# PiHAT_v0_3.net
KiCad netlist of a schematic drawn in EAGLE
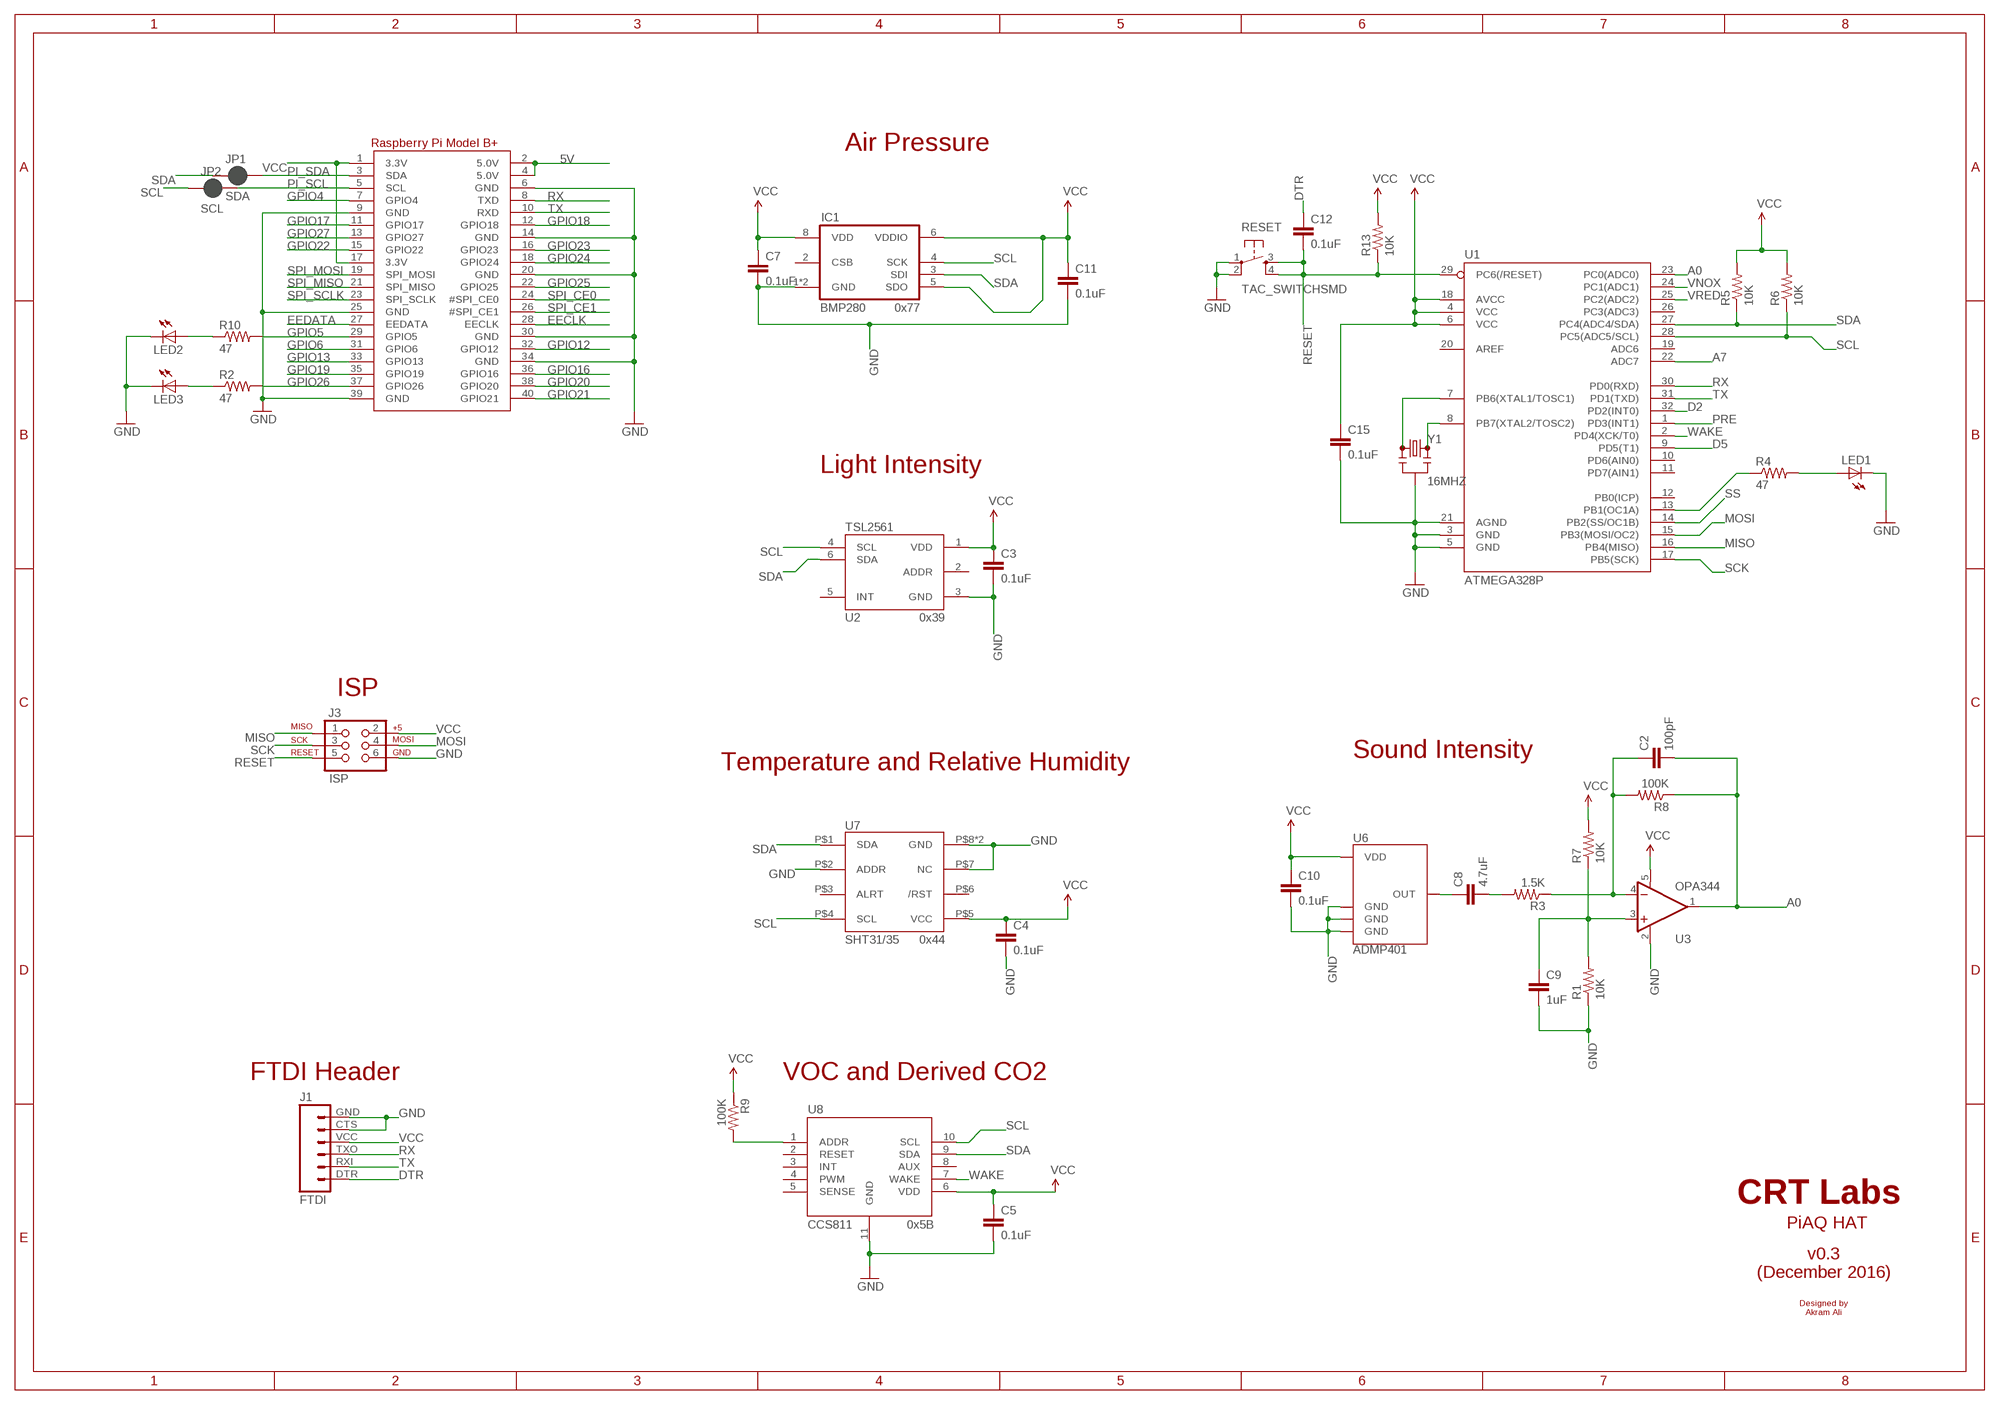
[diagram p0: schematic, sheet 1]

(export (version "E")
  (design (tool "Eeschema 10.0.6"))
  (components
    (comp (ref "C2")
      (value "100pF")
      (footprint "eagle-import:0805")
      (fields (field (name "MPN") "CC0805JRNPO9BN101"))
      (libsource (lib "eagle-import") (part "CAP0805"))
    )
    (comp (ref "C3")
      (value "0.1uF")
      (footprint "eagle-import:0805")
      (fields (field (name "MPN") "CC0603KRX7R7BB104"))
      (libsource (lib "eagle-import") (part "SparkFun-Passives_CAP0805"))
    )
    (comp (ref "C4")
      (value "0.1uF")
      (footprint "eagle-import:0805")
      (fields (field (name "MPN") "CC0603KRX7R7BB104"))
      (libsource (lib "eagle-import") (part "SparkFun-Passives_CAP0805"))
    )
    (comp (ref "C5")
      (value "0.1uF")
      (footprint "eagle-import:0805")
      (fields (field (name "MPN") "CC0603KRX7R7BB104"))
      (libsource (lib "eagle-import") (part "SparkFun-Passives_CAP0805"))
    )
    (comp (ref "C7")
      (value "0.1uF")
      (footprint "eagle-import:0805")
      (fields (field (name "MPN") "CC0603KRX7R7BB104"))
      (libsource (lib "eagle-import") (part "SparkFun-Passives_CAP0805"))
    )
    (comp (ref "C8")
      (value "4.7uF")
      (footprint "eagle-import:0805")
      (fields (field (name "MPN") "CC0805KKX5R8BB475"))
      (libsource (lib "eagle-import") (part "CAP0805"))
    )
    (comp (ref "C9")
      (value "1uF")
      (footprint "eagle-import:0805")
      (fields (field (name "MPN") "CC0805KKX7R7BB105"))
      (libsource (lib "eagle-import") (part "CAP0805"))
    )
    (comp (ref "C10")
      (value "0.1uF")
      (footprint "eagle-import:0805")
      (fields (field (name "MPN") "CC0603KRX7R7BB104"))
      (libsource (lib "eagle-import") (part "CAP0805"))
    )
    (comp (ref "C11")
      (value "0.1uF")
      (footprint "eagle-import:0805")
      (fields (field (name "MPN") "CC0603KRX7R7BB104"))
      (libsource (lib "eagle-import") (part "SparkFun-Passives_CAP0805"))
    )
    (comp (ref "C12")
      (value "0.1uF")
      (footprint "eagle-import:0805")
      (fields (field (name "MPN") "CC0603KRX7R7BB104"))
      (libsource (lib "eagle-import") (part "SparkFun-Passives_CAP0805"))
    )
    (comp (ref "C15")
      (value "0.1uF")
      (footprint "eagle-import:0805")
      (fields (field (name "MPN") "CC0603KRX7R7BB104"))
      (libsource (lib "eagle-import") (part "SparkFun-Passives_CAP0805"))
    )
    (comp (ref "IC1")
      (value "BMP280")
      (footprint "eagle-import:BMP280")
      (libsource (lib "eagle-import") (part "BMP280"))
    )
    (comp (ref "J1")
      (value "FTDI")
      (footprint "eagle-import:FTDI_BASIC")
      (libsource (lib "eagle-import") (part "FTDI_BASICPTH"))
    )
    (comp (ref "J3")
      (value "ISP")
      (footprint "eagle-import:2X3")
      (libsource (lib "eagle-import") (part "AVR_SPI_PRG_6PTH"))
    )
    (comp (ref "JP1")
      (value "SDA")
      (footprint "eagle-import:PAD-JUMPER-2-NC_BY_PASTE_YES_SILK_FULL_BOX")
      (libsource (lib "eagle-import") (part "JUMPER-PAD-2-NC_BY_PASTEFULL-BOX-SILK"))
    )
    (comp (ref "JP2")
      (value "SCL")
      (footprint "eagle-import:PAD-JUMPER-2-NC_BY_PASTE_YES_SILK_FULL_BOX")
      (libsource (lib "eagle-import") (part "JUMPER-PAD-2-NC_BY_PASTEFULL-BOX-SILK"))
    )
    (comp (ref "LED1")
      (value "LEDCHIPLED_0805")
      (footprint "eagle-import:CHIPLED_0805")
      (fields (field (name "MPN") "LTST-C170TBKT"))
      (libsource (lib "eagle-import") (part "LEDCHIPLED_0805"))
    )
    (comp (ref "LED2")
      (value "LEDCHIPLED_0805")
      (footprint "eagle-import:CHIPLED_0805")
      (fields (field (name "MPN") "LTST-C170TBKT"))
      (libsource (lib "eagle-import") (part "LEDCHIPLED_0805"))
    )
    (comp (ref "LED3")
      (value "LEDCHIPLED_0805")
      (footprint "eagle-import:CHIPLED_0805")
      (fields (field (name "MPN") "LTST-C170TBKT"))
      (libsource (lib "eagle-import") (part "LEDCHIPLED_0805"))
    )
    (comp (ref "R1")
      (value "10K")
      (footprint "eagle-import:0805")
      (fields (field (name "MPN") "RC0805JR-0710KL"))
      (libsource (lib "eagle-import") (part "RESISTOR0805-RES"))
    )
    (comp (ref "R2")
      (value "47")
      (footprint "eagle-import:0805")
      (fields (field (name "MPN") "RC0805JR-0747RL"))
      (libsource (lib "eagle-import") (part "SparkFun-Resistors_RESISTOR0805-RES"))
    )
    (comp (ref "R3")
      (value "1.5K")
      (footprint "eagle-import:0805")
      (fields (field (name "MPN") "RT0805BRD071K5L"))
      (libsource (lib "eagle-import") (part "RESISTOR0805-RES"))
    )
    (comp (ref "R4")
      (value "47")
      (footprint "eagle-import:0805")
      (fields (field (name "MPN") "RC0805JR-0747RL"))
      (libsource (lib "eagle-import") (part "SparkFun-Resistors_RESISTOR0805-RES"))
    )
    (comp (ref "R5")
      (value "10K")
      (footprint "eagle-import:0805")
      (fields (field (name "MPN") "RC0805JR-0710KL"))
      (libsource (lib "eagle-import") (part "SparkFun-Resistors_RESISTOR0805-RES"))
    )
    (comp (ref "R6")
      (value "10K")
      (footprint "eagle-import:0805")
      (fields (field (name "MPN") "RC0805JR-0710KL"))
      (libsource (lib "eagle-import") (part "SparkFun-Resistors_RESISTOR0805-RES"))
    )
    (comp (ref "R7")
      (value "10K")
      (footprint "eagle-import:0805")
      (fields (field (name "MPN") "RC0805JR-0710KL"))
      (libsource (lib "eagle-import") (part "RESISTOR0805-RES"))
    )
    (comp (ref "R8")
      (value "100K")
      (footprint "eagle-import:0805")
      (fields (field (name "MPN") "RC0805FR-07100KL"))
      (libsource (lib "eagle-import") (part "RESISTOR0805-RES"))
    )
    (comp (ref "R9")
      (value "100K")
      (footprint "eagle-import:0805")
      (fields (field (name "MPN") "RC0805FR-07100KL"))
      (libsource (lib "eagle-import") (part "RESISTOR0805-RES"))
    )
    (comp (ref "R10")
      (value "47")
      (footprint "eagle-import:0805")
      (fields (field (name "MPN") "RC0805JR-0747RL"))
      (libsource (lib "eagle-import") (part "SparkFun-Resistors_RESISTOR0805-RES"))
    )
    (comp (ref "R13")
      (value "10K")
      (footprint "eagle-import:0805")
      (fields (field (name "MPN") "RC0805JR-0710KL"))
      (libsource (lib "eagle-import") (part "RESISTOR0805-RES"))
    )
    (comp (ref "RESET")
      (value "TAC_SWITCHSMD")
      (footprint "eagle-import:TACTILE-SWITCH-SMD")
      (fields (field (name "MPN") "PTS525SM15SMTR2 LFS"))
      (libsource (lib "eagle-import") (part "TAC_SWITCHSMD"))
    )
    (comp (ref "RPI1")
      (value "RASPBERRYPI_BPLUS_HATSLOTS")
      (footprint "eagle-import:PI_HAT_SLOTS")
      (libsource (lib "eagle-import") (part "RASPBERRYPI_BPLUS_HATSLOTS"))
    )
    (comp (ref "U1")
      (value "ATMEGA328P")
      (footprint "eagle-import:TQFP32-08")
      (fields (field (name "MPN") "ATMEGA328PB-AU"))
      (libsource (lib "eagle-import") (part "ATMEGA328P_TQFP"))
    )
    (comp (ref "U2")
      (value "TSL2561")
      (footprint "eagle-import:FN-6")
      (fields (field (name "MPN") "TSL2561FN"))
      (libsource (lib "eagle-import") (part "TSL2561FN"))
    )
    (comp (ref "U3")
      (value "OPA344")
      (footprint "eagle-import:SOT23-5")
      (fields (field (name "MPN") "OPA344NA/3K"))
      (libsource (lib "eagle-import") (part "OPA344"))
    )
    (comp (ref "U6")
      (value "ADMP401")
      (footprint "eagle-import:ADMP401")
      (fields (field (name "MPN") "INMP401ACEZ-R7"))
      (libsource (lib "eagle-import") (part "ADMP401"))
    )
    (comp (ref "U7")
      (value "SHT31/35")
      (footprint "eagle-import:SHT3X")
      (fields (field (name "MPN") "SHT31-DIS-B"))
      (libsource (lib "eagle-import") (part "SHT31-DIS"))
    )
    (comp (ref "U8")
      (value "CCS811")
      (footprint "eagle-import:LGA")
      (libsource (lib "eagle-import") (part "CCS811-I2C"))
    )
    (comp (ref "Y1")
      (value "16MHZ")
      (footprint "eagle-import:RESONATOR-SMD")
      (fields (field (name "MPN") "CSTCE16M0V53-R0"))
      (libsource (lib "eagle-import") (part "RESONATOR16MHZ"))
    )
  )
  (nets
    (net (code "1") (name "/5V") (class "Default")
      (node (ref "RPI1") (pin "2") (pinfunction "5.0V_2") (pintype "power_in"))
      (node (ref "RPI1") (pin "4") (pinfunction "5.0V_4") (pintype "power_in"))
    )
    (net (code "2") (name "/EECLK") (class "Default")
      (node (ref "RPI1") (pin "28") (pinfunction "EECLK_28") (pintype "power_in"))
    )
    (net (code "3") (name "/EEDATA") (class "Default")
      (node (ref "RPI1") (pin "27") (pinfunction "EEDATA_27") (pintype "bidirectional"))
    )
    (net (code "4") (name "/GPIO4") (class "Default")
      (node (ref "RPI1") (pin "7") (pinfunction "GPIO4_7") (pintype "bidirectional"))
    )
    (net (code "5") (name "/GPIO5") (class "Default")
      (node (ref "R10") (pin "2") (pinfunction "2_2") (pintype "passive"))
      (node (ref "RPI1") (pin "29") (pinfunction "GPIO5_29") (pintype "bidirectional"))
    )
    (net (code "6") (name "/GPIO6") (class "Default")
      (node (ref "RPI1") (pin "31") (pinfunction "GPIO6_31") (pintype "power_in"))
    )
    (net (code "7") (name "/GPIO12") (class "Default")
      (node (ref "RPI1") (pin "32") (pinfunction "GPIO12_32") (pintype "bidirectional"))
    )
    (net (code "8") (name "/GPIO13") (class "Default")
      (node (ref "RPI1") (pin "33") (pinfunction "GPIO13_33") (pintype "bidirectional"))
    )
    (net (code "9") (name "/GPIO16") (class "Default")
      (node (ref "RPI1") (pin "36") (pinfunction "GPIO16_36") (pintype "power_in"))
    )
    (net (code "10") (name "/GPIO17") (class "Default")
      (node (ref "RPI1") (pin "11") (pinfunction "GPIO17_11") (pintype "bidirectional"))
    )
    (net (code "11") (name "/GPIO18") (class "Default")
      (node (ref "RPI1") (pin "12") (pinfunction "GPIO18_12") (pintype "bidirectional"))
    )
    (net (code "12") (name "/GPIO19") (class "Default")
      (node (ref "RPI1") (pin "35") (pinfunction "GPIO19_35") (pintype "bidirectional"))
    )
    (net (code "13") (name "/GPIO20") (class "Default")
      (node (ref "RPI1") (pin "38") (pinfunction "GPIO20_38") (pintype "bidirectional"))
    )
    (net (code "14") (name "/GPIO21") (class "Default")
      (node (ref "RPI1") (pin "40") (pinfunction "GPIO21_40") (pintype "bidirectional"))
    )
    (net (code "15") (name "/GPIO22") (class "Default")
      (node (ref "RPI1") (pin "15") (pinfunction "GPIO22_15") (pintype "bidirectional"))
    )
    (net (code "16") (name "/GPIO23") (class "Default")
      (node (ref "RPI1") (pin "16") (pinfunction "GPIO23_16") (pintype "bidirectional"))
    )
    (net (code "17") (name "/GPIO24") (class "Default")
      (node (ref "RPI1") (pin "18") (pinfunction "GPIO24_18") (pintype "bidirectional"))
    )
    (net (code "18") (name "/GPIO25") (class "Default")
      (node (ref "RPI1") (pin "22") (pinfunction "GPIO25_22") (pintype "bidirectional"))
    )
    (net (code "19") (name "/GPIO26") (class "Default")
      (node (ref "R2") (pin "2") (pinfunction "2_2") (pintype "passive"))
      (node (ref "RPI1") (pin "37") (pinfunction "GPIO26_37") (pintype "bidirectional"))
    )
    (net (code "20") (name "/GPIO27") (class "Default")
      (node (ref "RPI1") (pin "13") (pinfunction "GPIO27_13") (pintype "bidirectional"))
    )
    (net (code "21") (name "/PI_SCL") (class "Default")
      (node (ref "JP2") (pin "2") (pinfunction "2_2") (pintype "passive"))
      (node (ref "RPI1") (pin "5") (pinfunction "SCL_5") (pintype "bidirectional"))
    )
    (net (code "22") (name "/PI_SDA") (class "Default")
      (node (ref "JP1") (pin "2") (pinfunction "2_2") (pintype "passive"))
      (node (ref "RPI1") (pin "3") (pinfunction "SDA_3") (pintype "bidirectional"))
    )
    (net (code "23") (name "/SPI_CE0") (class "Default")
      (node (ref "RPI1") (pin "24") (pinfunction "#SPI_CE0_24") (pintype "bidirectional"))
    )
    (net (code "24") (name "/SPI_CE1") (class "Default")
      (node (ref "RPI1") (pin "26") (pinfunction "#SPI_CE1_26") (pintype "bidirectional"))
    )
    (net (code "25") (name "/SPI_MISO") (class "Default")
      (node (ref "RPI1") (pin "21") (pinfunction "SPI_MISO_21") (pintype "bidirectional"))
    )
    (net (code "26") (name "/SPI_MOSI") (class "Default")
      (node (ref "RPI1") (pin "19") (pinfunction "SPI_MOSI_19") (pintype "bidirectional"))
    )
    (net (code "27") (name "/SPI_SCLK") (class "Default")
      (node (ref "RPI1") (pin "23") (pinfunction "SPI_SCLK_23") (pintype "bidirectional"))
    )
    (net (code "28") (name "A0") (class "Default")
      (node (ref "C2") (pin "2") (pinfunction "2_2") (pintype "passive"))
      (node (ref "R8") (pin "1") (pinfunction "1_1") (pintype "passive"))
      (node (ref "U1") (pin "23") (pinfunction "PC0(ADC0)_23") (pintype "bidirectional"))
      (node (ref "U3") (pin "1") (pinfunction "OUT_1") (pintype "output"))
    )
    (net (code "29") (name "A7") (class "Default")
      (node (ref "U1") (pin "22") (pinfunction "ADC7_22") (pintype "bidirectional"))
    )
    (net (code "30") (name "D2") (class "Default")
      (node (ref "U1") (pin "32") (pinfunction "PD2(INT0)_32") (pintype "bidirectional"))
    )
    (net (code "31") (name "D5") (class "Default")
      (node (ref "U1") (pin "9") (pinfunction "PD5(T1)_9") (pintype "bidirectional"))
    )
    (net (code "32") (name "DTR") (class "Default")
      (node (ref "C12") (pin "1") (pinfunction "1_1") (pintype "passive"))
      (node (ref "J1") (pin "DTR") (pinfunction "1_DTR") (pintype "passive"))
    )
    (net (code "33") (name "GND") (class "Default")
      (node (ref "C10") (pin "2") (pinfunction "2_2") (pintype "passive"))
      (node (ref "C11") (pin "2") (pinfunction "2_2") (pintype "passive"))
      (node (ref "C15") (pin "2") (pinfunction "2_2") (pintype "passive"))
      (node (ref "C3") (pin "2") (pinfunction "2_2") (pintype "passive"))
      (node (ref "C4") (pin "2") (pinfunction "2_2") (pintype "passive"))
      (node (ref "C5") (pin "2") (pinfunction "2_2") (pintype "passive"))
      (node (ref "C7") (pin "2") (pinfunction "2_2") (pintype "passive"))
      (node (ref "C9") (pin "2") (pinfunction "2_2") (pintype "passive"))
      (node (ref "IC1") (pin "1") (pinfunction "GND_1") (pintype "power_in"))
      (node (ref "IC1") (pin "7") (pinfunction "GND_7") (pintype "power_in"))
      (node (ref "J1") (pin "CTS") (pinfunction "5_CTS") (pintype "passive"))
      (node (ref "J1") (pin "GND") (pinfunction "6_GND") (pintype "passive"))
      (node (ref "J3") (pin "6") (pinfunction "6_6") (pintype "passive"))
      (node (ref "LED1") (pin "C") (pinfunction "C_C") (pintype "passive"))
      (node (ref "LED2") (pin "C") (pinfunction "C_C") (pintype "passive"))
      (node (ref "LED3") (pin "C") (pinfunction "C_C") (pintype "passive"))
      (node (ref "R1") (pin "1") (pinfunction "1_1") (pintype "passive"))
      (node (ref "RESET") (pin "1") (pinfunction "1_1") (pintype "passive"))
      (node (ref "RESET") (pin "2") (pinfunction "2_2") (pintype "passive"))
      (node (ref "RPI1") (pin "14") (pinfunction "GND_14") (pintype "power_in"))
      (node (ref "RPI1") (pin "20") (pinfunction "GND_20") (pintype "power_in"))
      (node (ref "RPI1") (pin "25") (pinfunction "GND_25") (pintype "power_in"))
      (node (ref "RPI1") (pin "30") (pinfunction "GND_30") (pintype "bidirectional"))
      (node (ref "RPI1") (pin "34") (pinfunction "GND_34") (pintype "bidirectional"))
      (node (ref "RPI1") (pin "39") (pinfunction "GND_39") (pintype "power_in"))
      (node (ref "RPI1") (pin "6") (pinfunction "GND_6") (pintype "power_in"))
      (node (ref "RPI1") (pin "9") (pinfunction "GND_9") (pintype "power_in"))
      (node (ref "U1") (pin "21") (pinfunction "AGND_21") (pintype "bidirectional"))
      (node (ref "U1") (pin "3") (pinfunction "GND_3") (pintype "bidirectional"))
      (node (ref "U1") (pin "5") (pinfunction "GND_5") (pintype "bidirectional"))
      (node (ref "U2") (pin "3") (pinfunction "GND_3") (pintype "power_in"))
      (node (ref "U3") (pin "2") (pinfunction "V-_2") (pintype "power_in"))
      (node (ref "U6") (pin "2") (pinfunction "GND_2") (pintype "bidirectional"))
      (node (ref "U6") (pin "4") (pinfunction "GND_4") (pintype "bidirectional"))
      (node (ref "U6") (pin "6") (pinfunction "GND_6") (pintype "bidirectional"))
      (node (ref "U7") (pin "P$2") (pinfunction "ADDR_P$2") (pintype "bidirectional"))
      (node (ref "U7") (pin "P$7") (pinfunction "NC_P$7") (pintype "bidirectional"))
      (node (ref "U7") (pin "P$8") (pinfunction "GND_P$8") (pintype "bidirectional"))
      (node (ref "U7") (pin "PAD") (pinfunction "GND_PAD") (pintype "bidirectional"))
      (node (ref "U8") (pin "11") (pinfunction "GND_11") (pintype "bidirectional"))
      (node (ref "Y1") (pin "2") (pinfunction "2_2") (pintype "passive"))
    )
    (net (code "34") (name "MISO") (class "Default")
      (node (ref "J3") (pin "1") (pinfunction "1_1") (pintype "passive"))
      (node (ref "U1") (pin "16") (pinfunction "PB4(MISO)_16") (pintype "bidirectional"))
    )
    (net (code "35") (name "MOSI") (class "Default")
      (node (ref "J3") (pin "4") (pinfunction "4_4") (pintype "passive"))
      (node (ref "U1") (pin "15") (pinfunction "PB3(MOSI/OC2)_15") (pintype "bidirectional"))
    )
    (net (code "36") (name "Net-(C8-Pad2)") (class "Default")
      (node (ref "C8") (pin "2") (pinfunction "2_2") (pintype "passive"))
      (node (ref "R3") (pin "2") (pinfunction "2_2") (pintype "passive"))
    )
    (net (code "37") (name "Net-(LED1-PadA)") (class "Default")
      (node (ref "LED1") (pin "A") (pinfunction "A_A") (pintype "passive"))
      (node (ref "R4") (pin "2") (pinfunction "2_2") (pintype "passive"))
    )
    (net (code "38") (name "Net-(LED2-PadA)") (class "Default")
      (node (ref "LED2") (pin "A") (pinfunction "A_A") (pintype "passive"))
      (node (ref "R10") (pin "1") (pinfunction "1_1") (pintype "passive"))
    )
    (net (code "39") (name "Net-(LED3-PadA)") (class "Default")
      (node (ref "LED3") (pin "A") (pinfunction "A_A") (pintype "passive"))
      (node (ref "R2") (pin "1") (pinfunction "1_1") (pintype "passive"))
    )
    (net (code "40") (name "Net-(U1-PB1(OC1A))") (class "Default")
      (node (ref "R4") (pin "1") (pinfunction "1_1") (pintype "passive"))
      (node (ref "U1") (pin "13") (pinfunction "PB1(OC1A)_13") (pintype "bidirectional"))
    )
    (net (code "41") (name "Net-(U1-PB6(XTAL1{slash}TOSC1))") (class "Default")
      (node (ref "U1") (pin "7") (pinfunction "PB6(XTAL1/TOSC1)_7") (pintype "bidirectional"))
      (node (ref "Y1") (pin "1") (pinfunction "1_1") (pintype "passive"))
    )
    (net (code "42") (name "Net-(U1-PB7(XTAL2{slash}TOSC2))") (class "Default")
      (node (ref "U1") (pin "8") (pinfunction "PB7(XTAL2/TOSC2)_8") (pintype "bidirectional"))
      (node (ref "Y1") (pin "3") (pinfunction "3_3") (pintype "passive"))
    )
    (net (code "43") (name "Net-(U3-+IN)") (class "Default")
      (node (ref "C9") (pin "1") (pinfunction "1_1") (pintype "passive"))
      (node (ref "R1") (pin "2") (pinfunction "2_2") (pintype "passive"))
      (node (ref "R7") (pin "1") (pinfunction "1_1") (pintype "passive"))
      (node (ref "U3") (pin "3") (pinfunction "+IN_3") (pintype "input"))
    )
    (net (code "44") (name "Net-(U3--IN)") (class "Default")
      (node (ref "C2") (pin "1") (pinfunction "1_1") (pintype "passive"))
      (node (ref "R3") (pin "1") (pinfunction "1_1") (pintype "passive"))
      (node (ref "R8") (pin "2") (pinfunction "2_2") (pintype "passive"))
      (node (ref "U3") (pin "4") (pinfunction "-IN_4") (pintype "input"))
    )
    (net (code "45") (name "Net-(U6-OUT)") (class "Default")
      (node (ref "C8") (pin "1") (pinfunction "1_1") (pintype "passive"))
      (node (ref "U6") (pin "1") (pinfunction "OUT_1") (pintype "bidirectional"))
    )
    (net (code "46") (name "Net-(U8-ADDR)") (class "Default")
      (node (ref "R9") (pin "2") (pinfunction "2_2") (pintype "passive"))
      (node (ref "U8") (pin "1") (pinfunction "ADDR_1") (pintype "bidirectional"))
    )
    (net (code "47") (name "PRE") (class "Default")
      (node (ref "U1") (pin "1") (pinfunction "PD3(INT1)_1") (pintype "bidirectional"))
    )
    (net (code "48") (name "RESET") (class "Default")
      (node (ref "C12") (pin "2") (pinfunction "2_2") (pintype "passive"))
      (node (ref "J3") (pin "5") (pinfunction "5_5") (pintype "passive"))
      (node (ref "R13") (pin "1") (pinfunction "1_1") (pintype "passive"))
      (node (ref "RESET") (pin "3") (pinfunction "3_3") (pintype "passive"))
      (node (ref "RESET") (pin "4") (pinfunction "4_4") (pintype "passive"))
      (node (ref "U1") (pin "29") (pinfunction "PC6(/RESET)_29") (pintype "bidirectional"))
    )
    (net (code "49") (name "RX") (class "Default")
      (node (ref "J1") (pin "TXO") (pinfunction "3_TXO") (pintype "passive"))
      (node (ref "RPI1") (pin "8") (pinfunction "TXD_8") (pintype "output"))
      (node (ref "U1") (pin "30") (pinfunction "PD0(RXD)_30") (pintype "bidirectional"))
    )
    (net (code "50") (name "SCK") (class "Default")
      (node (ref "J3") (pin "3") (pinfunction "3_3") (pintype "passive"))
      (node (ref "U1") (pin "17") (pinfunction "PB5(SCK)_17") (pintype "bidirectional"))
    )
    (net (code "51") (name "SCL") (class "Default")
      (node (ref "IC1") (pin "4") (pinfunction "SCK_4") (pintype "bidirectional"))
      (node (ref "JP2") (pin "1") (pinfunction "1_1") (pintype "passive"))
      (node (ref "R6") (pin "1") (pinfunction "1_1") (pintype "passive"))
      (node (ref "U1") (pin "28") (pinfunction "PC5(ADC5/SCL)_28") (pintype "bidirectional"))
      (node (ref "U2") (pin "4") (pinfunction "SCL_4") (pintype "input"))
      (node (ref "U7") (pin "P$4") (pinfunction "SCL_P$4") (pintype "bidirectional"))
      (node (ref "U8") (pin "10") (pinfunction "SCL_10") (pintype "bidirectional"))
    )
    (net (code "52") (name "SDA") (class "Default")
      (node (ref "IC1") (pin "3") (pinfunction "SDI_3") (pintype "bidirectional"))
      (node (ref "JP1") (pin "1") (pinfunction "1_1") (pintype "passive"))
      (node (ref "R5") (pin "1") (pinfunction "1_1") (pintype "passive"))
      (node (ref "U1") (pin "27") (pinfunction "PC4(ADC4/SDA)_27") (pintype "bidirectional"))
      (node (ref "U2") (pin "6") (pinfunction "SDA_6") (pintype "bidirectional"))
      (node (ref "U7") (pin "P$1") (pinfunction "SDA_P$1") (pintype "bidirectional"))
      (node (ref "U8") (pin "9") (pinfunction "SDA_9") (pintype "bidirectional"))
    )
    (net (code "53") (name "SS") (class "Default")
      (node (ref "U1") (pin "14") (pinfunction "PB2(SS/OC1B)_14") (pintype "bidirectional"))
    )
    (net (code "54") (name "TX") (class "Default")
      (node (ref "J1") (pin "RXI") (pinfunction "2_RXI") (pintype "passive"))
      (node (ref "RPI1") (pin "10") (pinfunction "RXD_10") (pintype "bidirectional"))
      (node (ref "U1") (pin "31") (pinfunction "PD1(TXD)_31") (pintype "bidirectional"))
    )
    (net (code "55") (name "VCC") (class "Default")
      (node (ref "C10") (pin "1") (pinfunction "1_1") (pintype "passive"))
      (node (ref "C11") (pin "1") (pinfunction "1_1") (pintype "passive"))
      (node (ref "C15") (pin "1") (pinfunction "1_1") (pintype "passive"))
      (node (ref "C3") (pin "1") (pinfunction "1_1") (pintype "passive"))
      (node (ref "C4") (pin "1") (pinfunction "1_1") (pintype "passive"))
      (node (ref "C5") (pin "1") (pinfunction "1_1") (pintype "passive"))
      (node (ref "C7") (pin "1") (pinfunction "1_1") (pintype "passive"))
      (node (ref "IC1") (pin "5") (pinfunction "SDO_5") (pintype "input"))
      (node (ref "IC1") (pin "6") (pinfunction "VDDIO_6") (pintype "power_in"))
      (node (ref "IC1") (pin "8") (pinfunction "VDD_8") (pintype "power_in"))
      (node (ref "J1") (pin "VCC") (pinfunction "4_VCC") (pintype "passive"))
      (node (ref "J3") (pin "2") (pinfunction "2_2") (pintype "passive"))
      (node (ref "R13") (pin "2") (pinfunction "2_2") (pintype "passive"))
      (node (ref "R5") (pin "2") (pinfunction "2_2") (pintype "passive"))
      (node (ref "R6") (pin "2") (pinfunction "2_2") (pintype "passive"))
      (node (ref "R7") (pin "2") (pinfunction "2_2") (pintype "passive"))
      (node (ref "R9") (pin "1") (pinfunction "1_1") (pintype "passive"))
      (node (ref "RPI1") (pin "1") (pinfunction "3.3V_1") (pintype "power_in"))
      (node (ref "RPI1") (pin "17") (pinfunction "3.3V_17") (pintype "power_in"))
      (node (ref "U1") (pin "18") (pinfunction "AVCC_18") (pintype "bidirectional"))
      (node (ref "U1") (pin "4") (pinfunction "VCC_4") (pintype "bidirectional"))
      (node (ref "U1") (pin "6") (pinfunction "VCC_6") (pintype "bidirectional"))
      (node (ref "U2") (pin "1") (pinfunction "VDD_1") (pintype "power_in"))
      (node (ref "U3") (pin "5") (pinfunction "V+_5") (pintype "power_in"))
      (node (ref "U6") (pin "5") (pinfunction "VDD_5") (pintype "bidirectional"))
      (node (ref "U7") (pin "P$5") (pinfunction "VCC_P$5") (pintype "bidirectional"))
      (node (ref "U8") (pin "6") (pinfunction "VDD_6") (pintype "bidirectional"))
    )
    (net (code "56") (name "VNOX") (class "Default")
      (node (ref "U1") (pin "24") (pinfunction "PC1(ADC1)_24") (pintype "bidirectional"))
    )
    (net (code "57") (name "VRED") (class "Default")
      (node (ref "U1") (pin "25") (pinfunction "PC2(ADC2)_25") (pintype "bidirectional"))
    )
    (net (code "58") (name "WAKE") (class "Default")
      (node (ref "U1") (pin "2") (pinfunction "PD4(XCK/T0)_2") (pintype "bidirectional"))
      (node (ref "U8") (pin "7") (pinfunction "WAKE_7") (pintype "bidirectional"))
    )
    (net (code "59") (name "unconnected-(IC1-CSB-Pad2)") (class "Default")
      (node (ref "IC1") (pin "2") (pinfunction "CSB_2") (pintype "input"))
    )
    (net (code "60") (name "unconnected-(U1-ADC6-Pad19)") (class "Default")
      (node (ref "U1") (pin "19") (pinfunction "ADC6_19") (pintype "bidirectional"))
    )
    (net (code "61") (name "unconnected-(U1-AREF-Pad20)") (class "Default")
      (node (ref "U1") (pin "20") (pinfunction "AREF_20") (pintype "bidirectional"))
    )
    (net (code "62") (name "unconnected-(U1-PB0(ICP)-Pad12)") (class "Default")
      (node (ref "U1") (pin "12") (pinfunction "PB0(ICP)_12") (pintype "bidirectional"))
    )
    (net (code "63") (name "unconnected-(U1-PC3(ADC3)-Pad26)") (class "Default")
      (node (ref "U1") (pin "26") (pinfunction "PC3(ADC3)_26") (pintype "bidirectional"))
    )
    (net (code "64") (name "unconnected-(U1-PD6(AIN0)-Pad10)") (class "Default")
      (node (ref "U1") (pin "10") (pinfunction "PD6(AIN0)_10") (pintype "bidirectional"))
    )
    (net (code "65") (name "unconnected-(U1-PD7(AIN1)-Pad11)") (class "Default")
      (node (ref "U1") (pin "11") (pinfunction "PD7(AIN1)_11") (pintype "bidirectional"))
    )
    (net (code "66") (name "unconnected-(U2-ADDR-Pad2)") (class "Default")
      (node (ref "U2") (pin "2") (pinfunction "ADDR_2") (pintype "input"))
    )
    (net (code "67") (name "unconnected-(U2-INT-Pad5)") (class "Default")
      (node (ref "U2") (pin "5") (pinfunction "INT_5") (pintype "output"))
    )
    (net (code "68") (name "unconnected-(U7-ALRT-PadP$3)") (class "Default")
      (node (ref "U7") (pin "P$3") (pinfunction "ALRT_P$3") (pintype "bidirectional"))
    )
    (net (code "69") (name "unconnected-(U7-{slash}RST-PadP$6)") (class "Default")
      (node (ref "U7") (pin "P$6") (pinfunction "/RST_P$6") (pintype "bidirectional"))
    )
    (net (code "70") (name "unconnected-(U8-AUX-Pad8)") (class "Default")
      (node (ref "U8") (pin "8") (pinfunction "AUX_8") (pintype "bidirectional"))
    )
    (net (code "71") (name "unconnected-(U8-INT-Pad3)") (class "Default")
      (node (ref "U8") (pin "3") (pinfunction "INT_3") (pintype "bidirectional"))
    )
    (net (code "72") (name "unconnected-(U8-PWM-Pad4)") (class "Default")
      (node (ref "U8") (pin "4") (pinfunction "PWM_4") (pintype "bidirectional"))
    )
    (net (code "73") (name "unconnected-(U8-RESET-Pad2)") (class "Default")
      (node (ref "U8") (pin "2") (pinfunction "RESET_2") (pintype "bidirectional"))
    )
    (net (code "74") (name "unconnected-(U8-SENSE-Pad5)") (class "Default")
      (node (ref "U8") (pin "5") (pinfunction "SENSE_5") (pintype "bidirectional"))
    )
  )
)
